# M5amigo-RS-485-MAX485.net
KiCad netlist of a schematic drawn in EAGLE
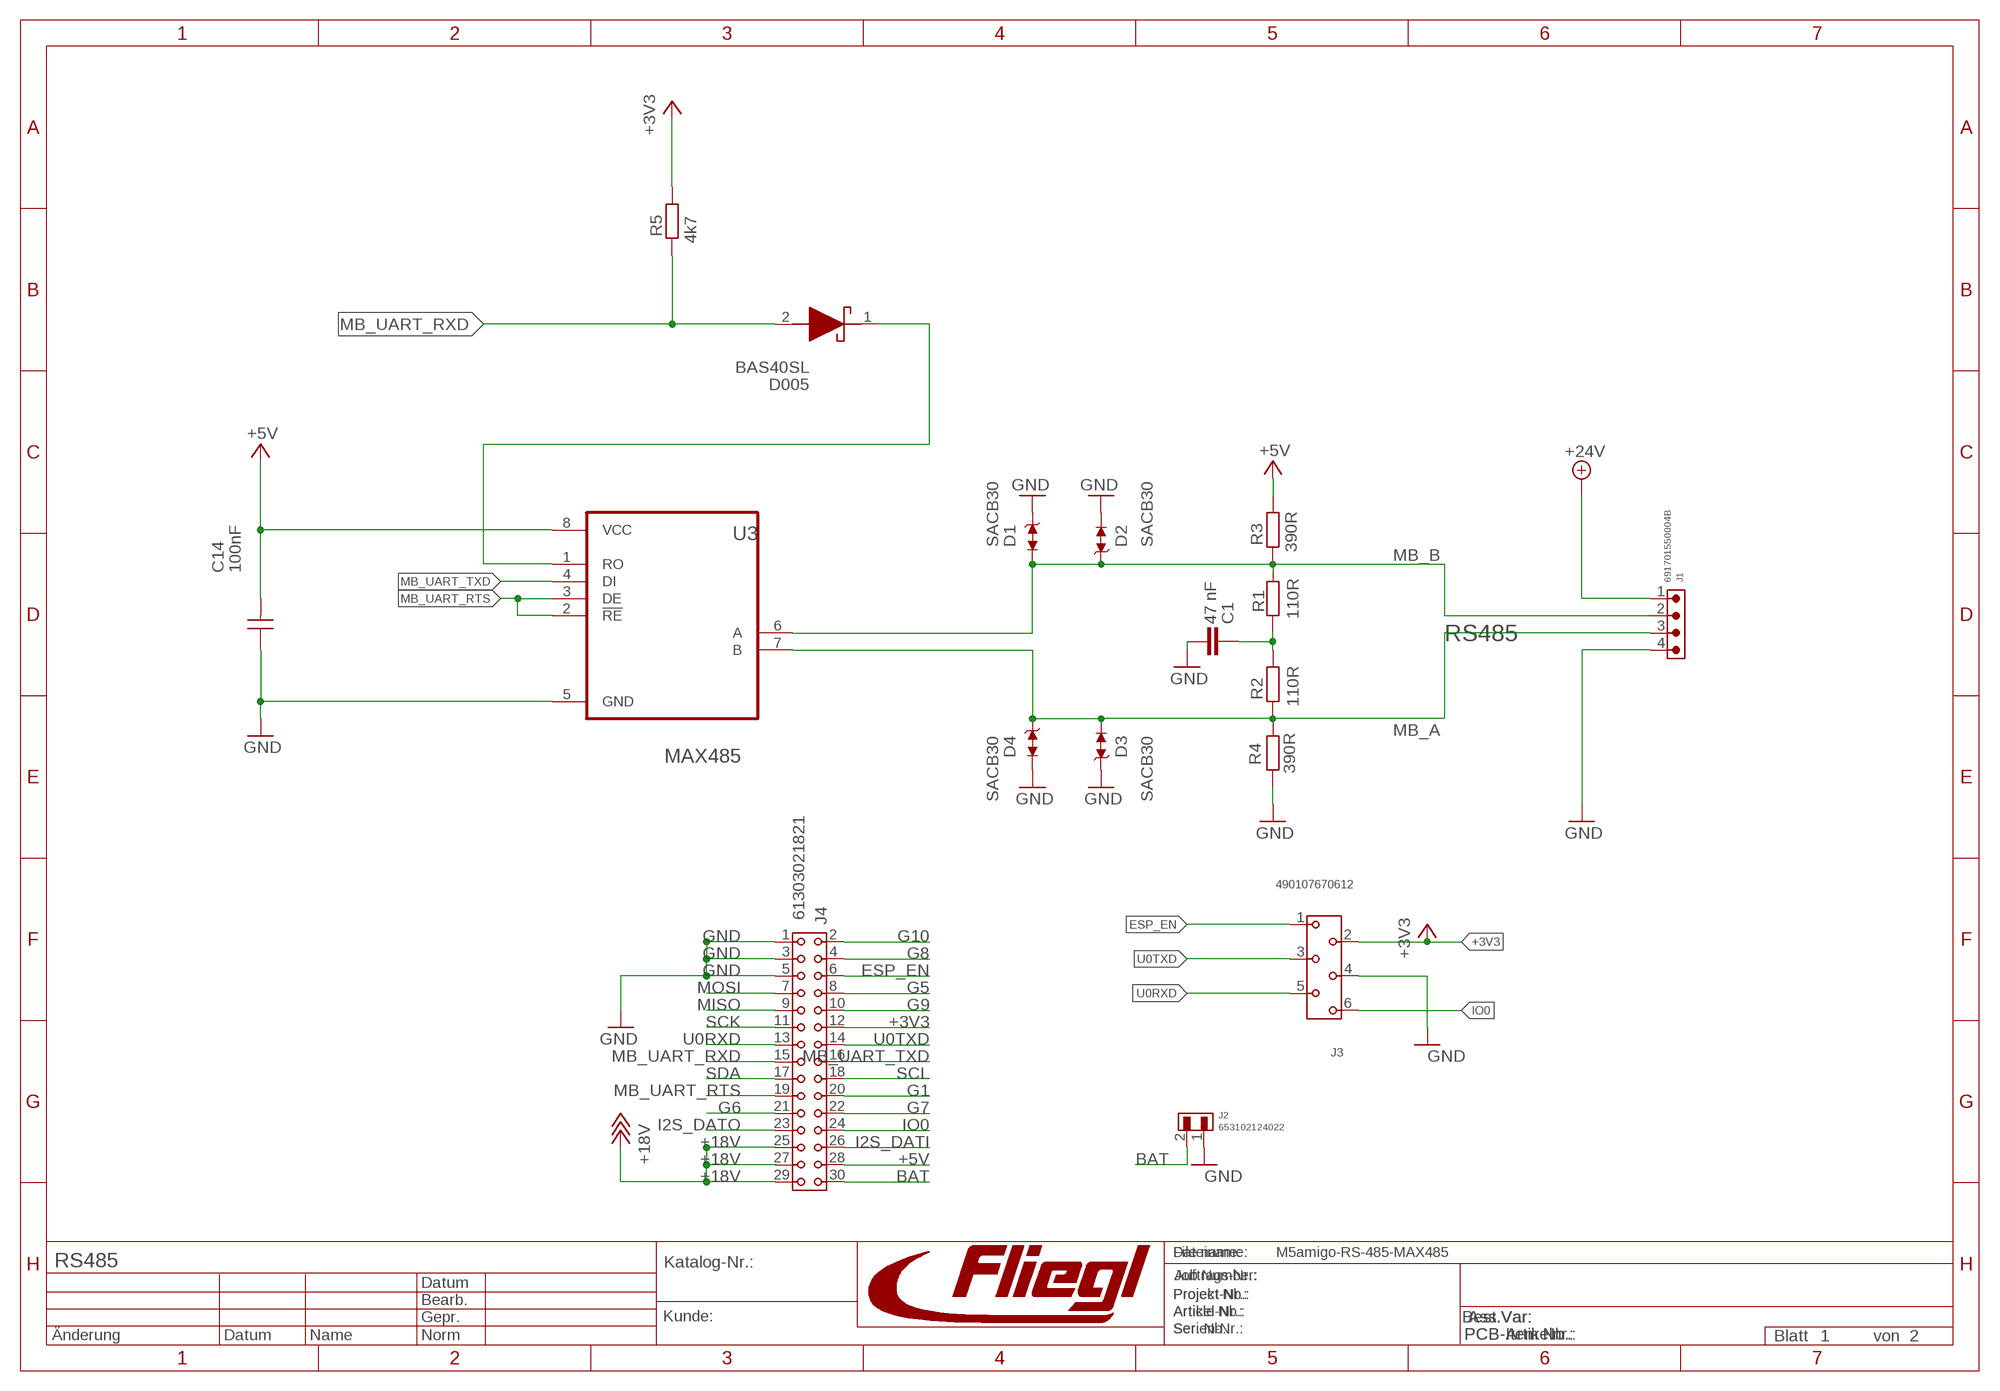
[diagram p0: schematic, sheet 1]
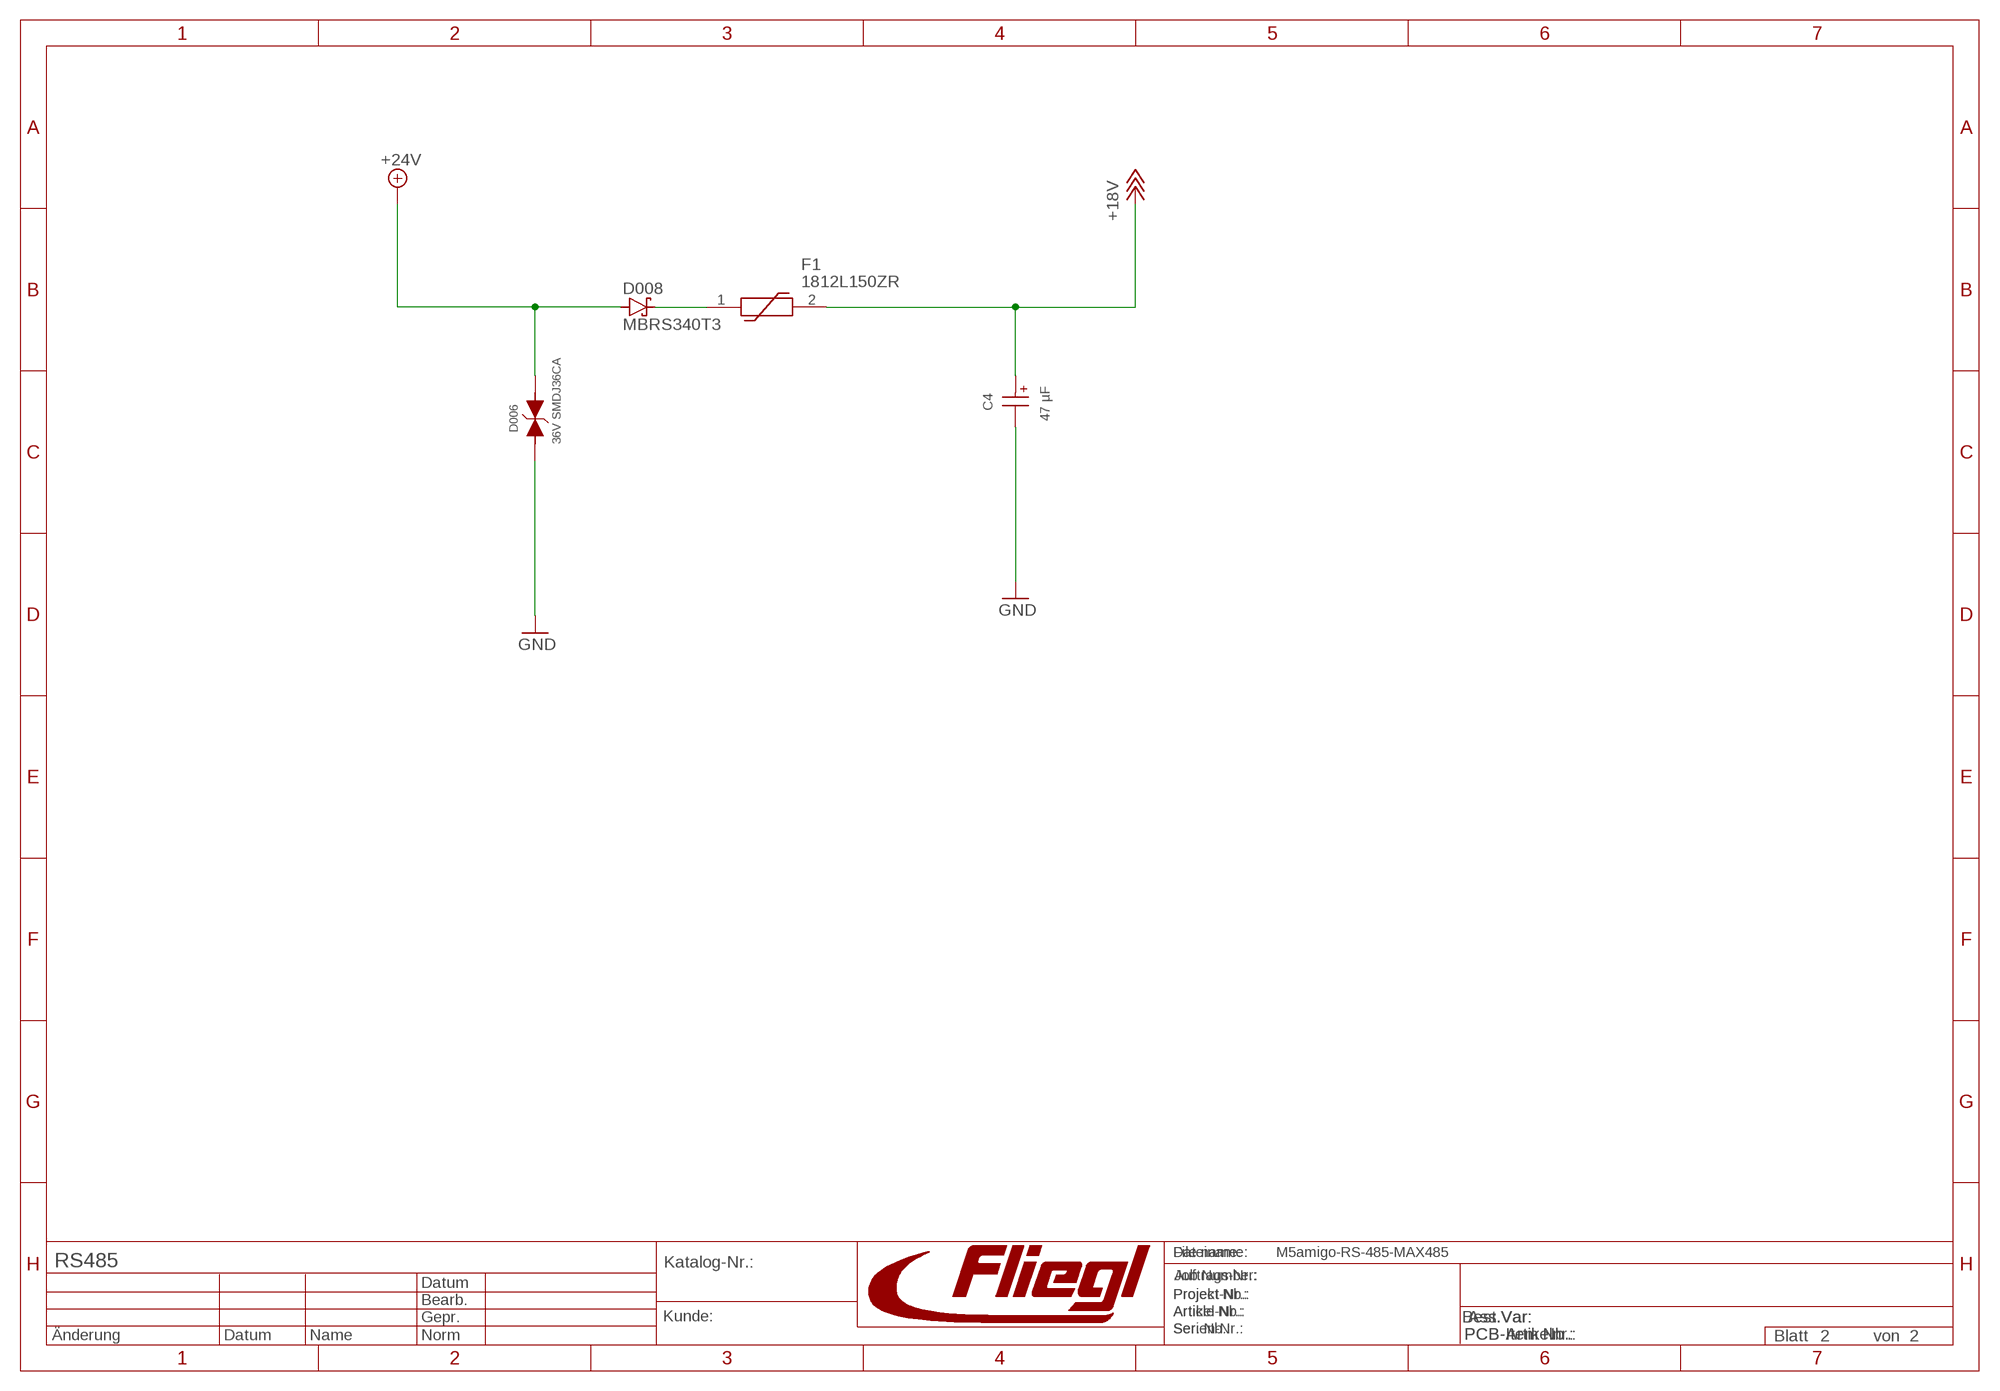
[diagram p1: schematic, sheet 2]

(export (version "E")
  (design (tool "Eeschema 10.0.6"))
  (components
    (comp (ref "C4")
      (value "47 µF")
      (footprint "eagle-import:WCAP-ASLL_6.3X7.7(DXL)")
      (libsource (lib "eagle-import") (part "WCAP-ASLL_6.3X7.7_865060645008"))
    )
    (comp (ref "D006")
      (value "36V SMDJ36CA")
      (footprint "eagle-import:WE-TVSP_DO-214AB_BIDIRECTIONAL")
      (libsource (lib "eagle-import") (part "WE-TVSP_DO-214AB_3000W_BI_824551361"))
    )
    (comp (ref "D008")
      (value "MBRS340T3")
      (footprint "eagle-import:SMC")
      (libsource (lib "eagle-import") (part "MBRS30T34"))
    )
    (comp (ref "F1")
      (value "1812L150ZR")
      (footprint "eagle-import:1812L010DR")
      (fields (field (name "MOUSER_PART_NUMBER") "576-1812L150ZR"))
      (libsource (lib "eagle-import") (part "1812L150ZR"))
    )
    (comp (ref "C1")
      (value "47 nF")
      (footprint "eagle-import:WCAP-CSGP_0402")
      (libsource (lib "eagle-import") (part "WCAP-CSGP_0402_25V(DC)_885012205054"))
    )
    (comp (ref "C14")
      (value "100nF")
      (footprint "eagle-import:WCAP-CSGP_1206_H0.8")
      (libsource (lib "eagle-import") (part "WCAP-CSGP_1206_H0.8_50V(DC)_885012208087"))
    )
    (comp (ref "D1")
      (value "SACB30")
      (footprint "eagle-import:DO214AA")
      (libsource (lib "eagle-import") (part "SACB30"))
    )
    (comp (ref "D2")
      (value "SACB30")
      (footprint "eagle-import:DO214AA")
      (libsource (lib "eagle-import") (part "SACB30"))
    )
    (comp (ref "D3")
      (value "SACB30")
      (footprint "eagle-import:DO214AA")
      (libsource (lib "eagle-import") (part "SACB30"))
    )
    (comp (ref "D4")
      (value "SACB30")
      (footprint "eagle-import:DO214AA")
      (libsource (lib "eagle-import") (part "SACB30"))
    )
    (comp (ref "D005")
      (value "BAS40SL")
      (footprint "eagle-import:SODFL1006X43N")
      (fields (field (name "MOUSER_PART_NUMBER") "512-BAS40SL"))
      (libsource (lib "eagle-import") (part "BAS40SL"))
    )
    (comp (ref "J1")
      (value "691701550004B")
      (footprint "eagle-import:691701550004B")
      (libsource (lib "eagle-import") (part "691701550004B"))
    )
    (comp (ref "J2")
      (value "653102124022")
      (footprint "eagle-import:653102124022")
      (libsource (lib "eagle-import") (part "653102124022"))
    )
    (comp (ref "J3")
      (value "490107670612")
      (footprint "eagle-import:490107670612_DEBUGGING")
      (libsource (lib "eagle-import") (part "490107670612_DEBUGGING"))
    )
    (comp (ref "J4")
      (value "61303021821")
      (footprint "eagle-import:61303021821")
      (libsource (lib "eagle-import") (part "6130XX21821_61303021821"))
    )
    (comp (ref "R1")
      (value "110R")
      (footprint "eagle-import:WCAP-CSRF_0402")
      (libsource (lib "eagle-import") (part "R-0402_110R"))
    )
    (comp (ref "R2")
      (value "110R")
      (footprint "eagle-import:WCAP-CSRF_0402")
      (libsource (lib "eagle-import") (part "R-0402_110R"))
    )
    (comp (ref "R3")
      (value "390R")
      (footprint "eagle-import:WCAP-CSMH_0603_R")
      (libsource (lib "eagle-import") (part "R-0603_390R"))
    )
    (comp (ref "R4")
      (value "390R")
      (footprint "eagle-import:WCAP-CSMH_0603_R")
      (libsource (lib "eagle-import") (part "R-0603_390R"))
    )
    (comp (ref "R5")
      (value "4k7")
      (footprint "eagle-import:WCAP-CSMH_0603_R")
      (libsource (lib "eagle-import") (part "R-0603_390R"))
    )
    (comp (ref "U3")
      (value "MAX485")
      (footprint "eagle-import:SOIC127P600X175-8N")
      (fields (field (name "MF") "Analog Devices") (field (name "MP") "MAX3485ECSA+T"))
      (libsource (lib "eagle-import") (part "MAX3485ECSA+T"))
    )
  )
  (nets
    (net (code "1") (name "+3V3") (class "Default")
      (node (ref "J3") (pin "2") (pinfunction "2_2") (pintype "passive"))
      (node (ref "J4") (pin "12") (pinfunction "12_12") (pintype "passive"))
      (node (ref "R5") (pin "2") (pinfunction "2_2") (pintype "passive"))
    )
    (net (code "2") (name "+5V") (class "Default")
      (node (ref "C14") (pin "2") (pinfunction "2_2") (pintype "passive"))
      (node (ref "J4") (pin "28") (pinfunction "28_28") (pintype "passive"))
      (node (ref "R3") (pin "2") (pinfunction "2_2") (pintype "passive"))
      (node (ref "U3") (pin "8") (pinfunction "VCC_8") (pintype "power_in"))
    )
    (net (code "3") (name "+18V") (class "Default")
      (node (ref "C4") (pin "1") (pinfunction "+_1") (pintype "passive"))
      (node (ref "F1") (pin "2") (pinfunction "2_2") (pintype "bidirectional"))
      (node (ref "J4") (pin "25") (pinfunction "25_25") (pintype "passive"))
      (node (ref "J4") (pin "27") (pinfunction "27_27") (pintype "passive"))
      (node (ref "J4") (pin "29") (pinfunction "29_29") (pintype "passive"))
    )
    (net (code "4") (name "+24V") (class "Default")
      (node (ref "D006") (pin "2") (pinfunction "2_2") (pintype "passive"))
      (node (ref "D008") (pin "A") (pinfunction "A_A") (pintype "passive"))
      (node (ref "J1") (pin "1") (pinfunction "1_1") (pintype "passive"))
    )
    (net (code "5") (name "BAT") (class "Default")
      (node (ref "J2") (pin "2") (pinfunction "2_2") (pintype "passive"))
      (node (ref "J4") (pin "30") (pinfunction "30_30") (pintype "passive"))
    )
    (net (code "6") (name "ESP_EN") (class "Default")
      (node (ref "J3") (pin "1") (pinfunction "1_1") (pintype "passive"))
      (node (ref "J4") (pin "6") (pinfunction "6_6") (pintype "passive"))
    )
    (net (code "7") (name "G1") (class "Default")
      (node (ref "J4") (pin "20") (pinfunction "20_20") (pintype "passive"))
    )
    (net (code "8") (name "G5") (class "Default")
      (node (ref "J4") (pin "8") (pinfunction "8_8") (pintype "passive"))
    )
    (net (code "9") (name "G6") (class "Default")
      (node (ref "J4") (pin "21") (pinfunction "21_21") (pintype "passive"))
    )
    (net (code "10") (name "G7") (class "Default")
      (node (ref "J4") (pin "22") (pinfunction "22_22") (pintype "passive"))
    )
    (net (code "11") (name "G8") (class "Default")
      (node (ref "J4") (pin "4") (pinfunction "4_4") (pintype "passive"))
    )
    (net (code "12") (name "G9") (class "Default")
      (node (ref "J4") (pin "10") (pinfunction "10_10") (pintype "passive"))
    )
    (net (code "13") (name "G10") (class "Default")
      (node (ref "J4") (pin "2") (pinfunction "2_2") (pintype "passive"))
    )
    (net (code "14") (name "GND") (class "Default")
      (node (ref "C1") (pin "2") (pinfunction "2_2") (pintype "passive"))
      (node (ref "C14") (pin "1") (pinfunction "1_1") (pintype "passive"))
      (node (ref "C4") (pin "2") (pinfunction "-_2") (pintype "passive"))
      (node (ref "D006") (pin "1") (pinfunction "1_1") (pintype "passive"))
      (node (ref "D1") (pin "C") (pinfunction "K_C") (pintype "passive"))
      (node (ref "D2") (pin "A") (pinfunction "KD_A") (pintype "passive"))
      (node (ref "D3") (pin "C") (pinfunction "K_C") (pintype "passive"))
      (node (ref "D4") (pin "A") (pinfunction "KD_A") (pintype "passive"))
      (node (ref "J1") (pin "4") (pinfunction "4_4") (pintype "passive"))
      (node (ref "J2") (pin "1") (pinfunction "1_1") (pintype "passive"))
      (node (ref "J3") (pin "4") (pinfunction "4_4") (pintype "passive"))
      (node (ref "J4") (pin "1") (pinfunction "1_1") (pintype "passive"))
      (node (ref "J4") (pin "3") (pinfunction "3_3") (pintype "passive"))
      (node (ref "J4") (pin "5") (pinfunction "5_5") (pintype "passive"))
      (node (ref "R4") (pin "1") (pinfunction "1_1") (pintype "passive"))
      (node (ref "U3") (pin "5") (pinfunction "GND_5") (pintype "power_in"))
    )
    (net (code "15") (name "I2S_DATI") (class "Default")
      (node (ref "J4") (pin "26") (pinfunction "26_26") (pintype "passive"))
    )
    (net (code "16") (name "I2S_DATO") (class "Default")
      (node (ref "J4") (pin "23") (pinfunction "23_23") (pintype "passive"))
    )
    (net (code "17") (name "IO0") (class "Default")
      (node (ref "J3") (pin "6") (pinfunction "6_6") (pintype "passive"))
      (node (ref "J4") (pin "24") (pinfunction "24_24") (pintype "passive"))
    )
    (net (code "18") (name "MB_A") (class "Default")
      (node (ref "D3") (pin "A") (pinfunction "KD_A") (pintype "passive"))
      (node (ref "D4") (pin "C") (pinfunction "K_C") (pintype "passive"))
      (node (ref "J1") (pin "3") (pinfunction "3_3") (pintype "passive"))
      (node (ref "R2") (pin "1") (pinfunction "1_1") (pintype "passive"))
      (node (ref "R4") (pin "2") (pinfunction "2_2") (pintype "passive"))
      (node (ref "U3") (pin "7") (pinfunction "B_7") (pintype "bidirectional"))
    )
    (net (code "19") (name "MB_B") (class "Default")
      (node (ref "D1") (pin "A") (pinfunction "KD_A") (pintype "passive"))
      (node (ref "D2") (pin "C") (pinfunction "K_C") (pintype "passive"))
      (node (ref "J1") (pin "2") (pinfunction "2_2") (pintype "passive"))
      (node (ref "R1") (pin "2") (pinfunction "2_2") (pintype "passive"))
      (node (ref "R3") (pin "1") (pinfunction "1_1") (pintype "passive"))
      (node (ref "U3") (pin "6") (pinfunction "A_6") (pintype "bidirectional"))
    )
    (net (code "20") (name "MB_UART_RTS") (class "Default")
      (node (ref "J4") (pin "19") (pinfunction "19_19") (pintype "passive"))
      (node (ref "U3") (pin "2") (pinfunction "~{RE}_2") (pintype "input"))
      (node (ref "U3") (pin "3") (pinfunction "DE_3") (pintype "input"))
    )
    (net (code "21") (name "MB_UART_RXD") (class "Default")
      (node (ref "D005") (pin "2") (pinfunction "A_2") (pintype "bidirectional"))
      (node (ref "J4") (pin "15") (pinfunction "15_15") (pintype "passive"))
      (node (ref "R5") (pin "1") (pinfunction "1_1") (pintype "passive"))
    )
    (net (code "22") (name "MB_UART_TXD") (class "Default")
      (node (ref "J4") (pin "16") (pinfunction "16_16") (pintype "passive"))
      (node (ref "U3") (pin "4") (pinfunction "DI_4") (pintype "input"))
    )
    (net (code "23") (name "MISO") (class "Default")
      (node (ref "J4") (pin "9") (pinfunction "9_9") (pintype "passive"))
    )
    (net (code "24") (name "MOSI") (class "Default")
      (node (ref "J4") (pin "7") (pinfunction "7_7") (pintype "passive"))
    )
    (net (code "25") (name "Net-(C1-Pad1)") (class "Default")
      (node (ref "C1") (pin "1") (pinfunction "1_1") (pintype "passive"))
      (node (ref "R1") (pin "1") (pinfunction "1_1") (pintype "passive"))
      (node (ref "R2") (pin "2") (pinfunction "2_2") (pintype "passive"))
    )
    (net (code "26") (name "Net-(D005-K)") (class "Default")
      (node (ref "D005") (pin "1") (pinfunction "K_1") (pintype "bidirectional"))
      (node (ref "U3") (pin "1") (pinfunction "RO_1") (pintype "output"))
    )
    (net (code "27") (name "Net-(D008-PadC)") (class "Default")
      (node (ref "D008") (pin "C") (pinfunction "C_C") (pintype "passive"))
      (node (ref "F1") (pin "1") (pinfunction "1_1") (pintype "bidirectional"))
    )
    (net (code "28") (name "SCK") (class "Default")
      (node (ref "J4") (pin "11") (pinfunction "11_11") (pintype "passive"))
    )
    (net (code "29") (name "SCL") (class "Default")
      (node (ref "J4") (pin "18") (pinfunction "18_18") (pintype "passive"))
    )
    (net (code "30") (name "SDA") (class "Default")
      (node (ref "J4") (pin "17") (pinfunction "17_17") (pintype "passive"))
    )
    (net (code "31") (name "U0RXD") (class "Default")
      (node (ref "J3") (pin "5") (pinfunction "5_5") (pintype "passive"))
      (node (ref "J4") (pin "13") (pinfunction "13_13") (pintype "passive"))
    )
    (net (code "32") (name "U0TXD") (class "Default")
      (node (ref "J3") (pin "3") (pinfunction "3_3") (pintype "passive"))
      (node (ref "J4") (pin "14") (pinfunction "14_14") (pintype "passive"))
    )
  )
)
